# Mechatronic.net
KiCad netlist of a schematic drawn in Altium Designer
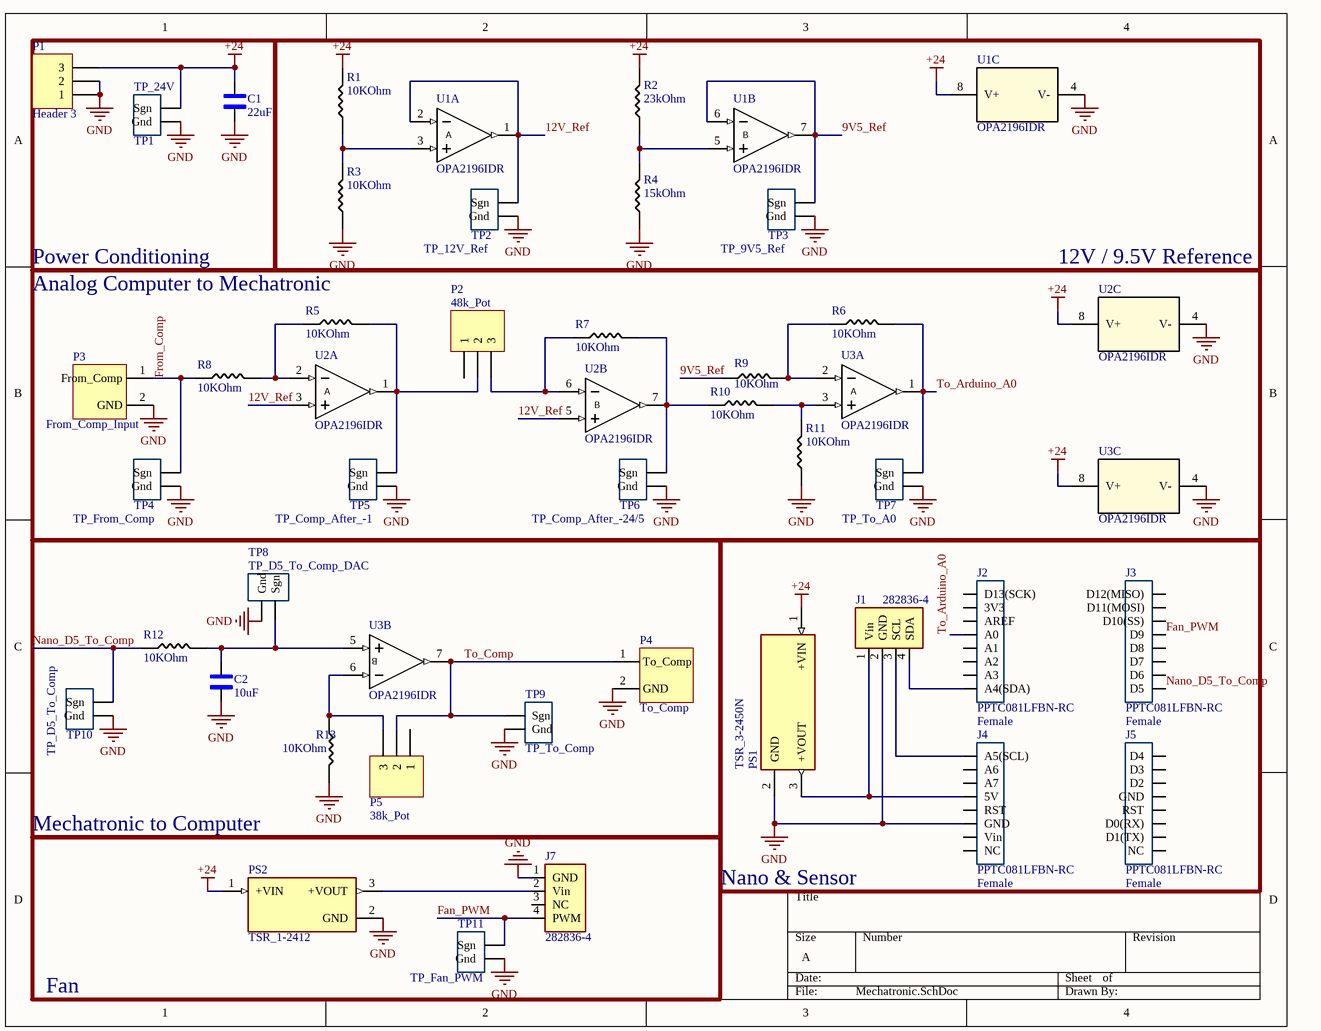
[diagram p0: Mechatronic.SchDoc]

(export (version "E")
  (design (tool "Eeschema 10.0.6"))
  (components
    (comp (ref "C1")
      (value "22uF")
      (footprint "1206_Passive_Capacitor")
      (description "22uF ±10% 25V X5R 1206 Multilayer Ceramic Capacitors MLCC - SMD/SMT RoHS")
      (fields (field (name "MFR PART #") "CL31A226KAHNNNE") (field (name "LCSC PART#") "C12891"))
      (libsource (lib "ECEN5730Lib_2023_05_DS") (part "C_22uF_1206"))
    )
    (comp (ref "C2")
      (value "10uF")
      (footprint "1206_Passive_Capacitor")
      (description "10uF ±10% 50V X5R 1206 Multilayer Ceramic Capacitors MLCC - SMD/SMT RoHS")
      (fields (field (name "LCSC PART#") "C13585") (field (name "MFR PART #") "CL31A106KBHNNNE"))
      (libsource (lib "ECEN5730Lib_2023_05_DS") (part "C_10uF_1206"))
    )
    (comp (ref "J1")
      (value "282836-4")
      (footprint "TE_282836-4")
      (description "4 Position Wire to Board Terminal Block Horizontal with Board 0.197 (5.00mm) Through Hole")
      (fields (field (name "MF") "TE Connectivity"))
      (libsource (lib "") (part "282836-4_1"))
    )
    (comp (ref "J2")
      (value "PPTC081LFBN-RC")
      (footprint "8_PIN_100MIL - Female")
      (description "8 Position Header Connector 0.100\" (2.54mm) Through Hole Tin")
      (fields (field (name "LCSC PART#") "C27438") (field (name "ALTIUM_VALUE") "Female"))
      (libsource (lib "") (part "JF_8_PIN_FEMALE_3"))
    )
    (comp (ref "J3")
      (value "PPTC081LFBN-RC")
      (footprint "8_PIN_100MIL - Female")
      (description "8 Position Header Connector 0.100\" (2.54mm) Through Hole Tin")
      (fields (field (name "LCSC PART#") "C27438") (field (name "ALTIUM_VALUE") "Female"))
      (libsource (lib "ECEN5730Lib_2023_05_DS") (part "JF_8_PIN_FEMALE"))
    )
    (comp (ref "J4")
      (value "PPTC081LFBN-RC")
      (footprint "8_PIN_100MIL - Female")
      (description "8 Position Header Connector 0.100\" (2.54mm) Through Hole Tin")
      (fields (field (name "LCSC PART#") "C27438") (field (name "ALTIUM_VALUE") "Female"))
      (libsource (lib "") (part "JF_8_PIN_FEMALE_1"))
    )
    (comp (ref "J5")
      (value "PPTC081LFBN-RC")
      (footprint "8_PIN_100MIL - Female")
      (description "8 Position Header Connector 0.100\" (2.54mm) Through Hole Tin")
      (fields (field (name "LCSC PART#") "C27438") (field (name "ALTIUM_VALUE") "Female"))
      (libsource (lib "") (part "JF_8_PIN_FEMALE_2"))
    )
    (comp (ref "J7")
      (value "282836-4")
      (footprint "TE_282836-4")
      (description "4 Position Wire to Board Terminal Block Horizontal with Board 0.197 (5.00mm) Through Hole")
      (fields (field (name "MF") "TE Connectivity"))
      (libsource (lib "282836-4") (part "282836-4"))
    )
    (comp (ref "P1")
      (value "Header 3")
      (footprint "HDR1X3")
      (description "Header, 3-Pin")
      (fields (field (name "PUBLISHER") "Altium Limited"))
      (libsource (lib "") (part "Header 3_1"))
    )
    (comp (ref "P2")
      (value "48k_Pot")
      (footprint "HDR1X3")
      (description "Header, 3-Pin")
      (fields (field (name "PUBLISHER") "Altium Limited"))
      (libsource (lib "") (part "Header 3_2"))
    )
    (comp (ref "P3")
      (value "From_Comp_Input")
      (footprint "P_Terminal block 3.5mm-pitch")
      (description "Green Straight pin 3.5mm  pitch; P=3.5mm  Screw terminal ROHS")
      (fields (field (name "MFR PART #") "KF350-3.5-2P") (field (name "MANUFACTURER") "Cixi Kefa Elec"))
      (libsource (lib "") (part "P_Terminal block_1"))
    )
    (comp (ref "P4")
      (value "To_Comp")
      (footprint "P_Terminal block 3.5mm-pitch")
      (description "Green Straight pin 3.5mm  pitch; P=3.5mm  Screw terminal ROHS")
      (fields (field (name "MFR PART #") "KF350-3.5-2P") (field (name "MANUFACTURER") "Cixi Kefa Elec"))
      (libsource (lib "ECEN5730Lib_2023_05_DS") (part "P_Terminal block"))
    )
    (comp (ref "P5")
      (value "38k_Pot")
      (footprint "HDR1X3")
      (description "Header, 3-Pin")
      (fields (field (name "PUBLISHER") "Altium Limited"))
      (libsource (lib "Miscellaneous Connectors") (part "Header 3"))
    )
    (comp (ref "PS1")
      (value "TSR_3-2450N")
      (footprint "CONV_TSR_3-2450N")
      (fields (field (name "MF") "{'manufacturer': u'Traco Power'}"))
      (libsource (lib "TSR_3-2450N") (part "TSR_3-2450N"))
    )
    (comp (ref "PS2")
      (value "TSR_1-2412")
      (footprint "CONV_TSR_1-2412")
      (libsource (lib "TSR_1-2412") (part "TSR_1-2412"))
    )
    (comp (ref "R1")
      (value "10KOhm")
      (footprint "1206_Passive_Resitor")
      (description "10 kOhms ±5% 0.25W, 1/4W Chip Resistor 1206 (3216 Metric) Automotive AEC-Q200 Thick Film")
      (fields (field (name "MFR PART #") "RMCF1206FT10K0") (field (name "LCSC PART#") "C17902"))
      (libsource (lib "ECEN5730Lib_2023_05_DS") (part "R_10KOhm_1206"))
    )
    (comp (ref "R2")
      (value "23kOhm")
      (footprint "1206_Passive_Resitor")
      (description "CHIP RESISTOR - SURFACE MOUNT 0OHMS ±1% 1/4W 1206 ROHS")
      (fields (field (name "MFR PART #") "1206W4F0000T5E") (field (name "LCSC PART#") "C17888"))
      (libsource (lib "Capstone_Stock_Library_R2") (part "R_0_1206"))
    )
    (comp (ref "R3")
      (value "10KOhm")
      (footprint "1206_Passive_Resitor")
      (description "10 kOhms ±5% 0.25W, 1/4W Chip Resistor 1206 (3216 Metric) Automotive AEC-Q200 Thick Film")
      (fields (field (name "MFR PART #") "RMCF1206FT10K0") (field (name "LCSC PART#") "C17902"))
      (libsource (lib "ECEN5730Lib_2023_05_DS") (part "R_10KOhm_1206"))
    )
    (comp (ref "R4")
      (value "15kOhm")
      (footprint "1206_Passive_Resitor")
      (description "CHIP RESISTOR - SURFACE MOUNT 0OHMS ±1% 1/4W 1206 ROHS")
      (fields (field (name "MFR PART #") "1206W4F0000T5E") (field (name "LCSC PART#") "C17888"))
      (libsource (lib "Capstone_Stock_Library_R2") (part "R_0_1206"))
    )
    (comp (ref "R5")
      (value "10KOhm")
      (footprint "1206_Passive_Resitor")
      (description "10 kOhms ±5% 0.25W, 1/4W Chip Resistor 1206 (3216 Metric) Automotive AEC-Q200 Thick Film")
      (fields (field (name "MFR PART #") "RMCF1206FT10K0") (field (name "LCSC PART#") "C17902"))
      (libsource (lib "ECEN5730Lib_2023_05_DS") (part "R_10KOhm_1206"))
    )
    (comp (ref "R6")
      (value "10KOhm")
      (footprint "1206_Passive_Resitor")
      (description "10 kOhms ±5% 0.25W, 1/4W Chip Resistor 1206 (3216 Metric) Automotive AEC-Q200 Thick Film")
      (fields (field (name "MFR PART #") "RMCF1206FT10K0") (field (name "LCSC PART#") "C17902"))
      (libsource (lib "ECEN5730Lib_2023_05_DS") (part "R_10KOhm_1206"))
    )
    (comp (ref "R7")
      (value "10KOhm")
      (footprint "1206_Passive_Resitor")
      (description "10 kOhms ±5% 0.25W, 1/4W Chip Resistor 1206 (3216 Metric) Automotive AEC-Q200 Thick Film")
      (fields (field (name "MFR PART #") "RMCF1206FT10K0") (field (name "LCSC PART#") "C17902"))
      (libsource (lib "ECEN5730Lib_2023_05_DS") (part "R_10KOhm_1206"))
    )
    (comp (ref "R8")
      (value "10KOhm")
      (footprint "1206_Passive_Resitor")
      (description "10 kOhms ±5% 0.25W, 1/4W Chip Resistor 1206 (3216 Metric) Automotive AEC-Q200 Thick Film")
      (fields (field (name "MFR PART #") "RMCF1206FT10K0") (field (name "LCSC PART#") "C17902"))
      (libsource (lib "ECEN5730Lib_2023_05_DS") (part "R_10KOhm_1206"))
    )
    (comp (ref "R9")
      (value "10KOhm")
      (footprint "1206_Passive_Resitor")
      (description "10 kOhms ±5% 0.25W, 1/4W Chip Resistor 1206 (3216 Metric) Automotive AEC-Q200 Thick Film")
      (fields (field (name "MFR PART #") "RMCF1206FT10K0") (field (name "LCSC PART#") "C17902"))
      (libsource (lib "ECEN5730Lib_2023_05_DS") (part "R_10KOhm_1206"))
    )
    (comp (ref "R10")
      (value "10KOhm")
      (footprint "1206_Passive_Resitor")
      (description "10 kOhms ±5% 0.25W, 1/4W Chip Resistor 1206 (3216 Metric) Automotive AEC-Q200 Thick Film")
      (fields (field (name "MFR PART #") "RMCF1206FT10K0") (field (name "LCSC PART#") "C17902"))
      (libsource (lib "ECEN5730Lib_2023_05_DS") (part "R_10KOhm_1206"))
    )
    (comp (ref "R11")
      (value "10KOhm")
      (footprint "1206_Passive_Resitor")
      (description "10 kOhms ±5% 0.25W, 1/4W Chip Resistor 1206 (3216 Metric) Automotive AEC-Q200 Thick Film")
      (fields (field (name "MFR PART #") "RMCF1206FT10K0") (field (name "LCSC PART#") "C17902"))
      (libsource (lib "ECEN5730Lib_2023_05_DS") (part "R_10KOhm_1206"))
    )
    (comp (ref "R12")
      (value "10KOhm")
      (footprint "1206_Passive_Resitor")
      (description "10 kOhms ±5% 0.25W, 1/4W Chip Resistor 1206 (3216 Metric) Automotive AEC-Q200 Thick Film")
      (fields (field (name "MFR PART #") "RMCF1206FT10K0") (field (name "LCSC PART#") "C17902"))
      (libsource (lib "ECEN5730Lib_2023_05_DS") (part "R_10KOhm_1206"))
    )
    (comp (ref "R13")
      (value "10KOhm")
      (footprint "1206_Passive_Resitor")
      (description "10 kOhms ±5% 0.25W, 1/4W Chip Resistor 1206 (3216 Metric) Automotive AEC-Q200 Thick Film")
      (fields (field (name "MFR PART #") "RMCF1206FT10K0") (field (name "LCSC PART#") "C17902"))
      (libsource (lib "ECEN5730Lib_2023_05_DS") (part "R_10KOhm_1206"))
    )
    (comp (ref "TP1")
      (value "TP_24V")
      (footprint "TP10x_Probe")
      (description "Test Point 300 mil centers")
      (libsource (lib "") (part "TP_10x_Probe_1"))
    )
    (comp (ref "TP2")
      (value "TP_12V_Ref")
      (footprint "TP10x_Probe")
      (description "Test Point 300 mil centers")
      (libsource (lib "") (part "TP_10x_Probe_1"))
    )
    (comp (ref "TP3")
      (value "TP_9V5_Ref")
      (footprint "TP10x_Probe")
      (description "Test Point 300 mil centers")
      (libsource (lib "") (part "TP_10x_Probe_1"))
    )
    (comp (ref "TP4")
      (value "TP_From_Comp")
      (footprint "TP10x_Probe")
      (description "Test Point 300 mil centers")
      (libsource (lib "") (part "TP_10x_Probe_1"))
    )
    (comp (ref "TP5")
      (value "TP_Comp_After_-1")
      (footprint "TP10x_Probe")
      (description "Test Point 300 mil centers")
      (libsource (lib "") (part "TP_10x_Probe_1"))
    )
    (comp (ref "TP6")
      (value "TP_Comp_After_-24/5")
      (footprint "TP10x_Probe")
      (description "Test Point 300 mil centers")
      (libsource (lib "") (part "TP_10x_Probe_1"))
    )
    (comp (ref "TP7")
      (value "TP_To_A0")
      (footprint "TP10x_Probe")
      (description "Test Point 300 mil centers")
      (libsource (lib "") (part "TP_10x_Probe_1"))
    )
    (comp (ref "TP8")
      (value "TP_D5_To_Comp_DAC")
      (footprint "TP10x_Probe")
      (description "Test Point 300 mil centers")
      (libsource (lib "ECEN5730Lib_2023_05_DS") (part "TP_10x_Probe"))
    )
    (comp (ref "TP9")
      (value "TP_To_Comp")
      (footprint "TP10x_Probe")
      (description "Test Point 300 mil centers")
      (libsource (lib "ECEN5730Lib_2023_05_DS") (part "TP_10x_Probe"))
    )
    (comp (ref "TP10")
      (value "TP_D5_To_Comp")
      (footprint "TP10x_Probe")
      (description "Test Point 300 mil centers")
      (libsource (lib "") (part "TP_10x_Probe_1"))
    )
    (comp (ref "TP11")
      (value "TP_Fan_PWM")
      (footprint "TP10x_Probe")
      (description "Test Point 300 mil centers")
      (libsource (lib "") (part "TP_10x_Probe_1"))
    )
    (comp (ref "U1")
      (value "OPA2196IDR")
      (footprint "D0008A_N")
      (description "Dual, 36-V, low power, all-purpose amplifier with mux-friendly input 8-SOIC -40 to 125")
      (fields (field (name "COPYRIGHT") "Copyright (C) 2026 Ultra Librarian. All rights reserved."))
      (libsource (lib "Integrated_Library1") (part "OPA2196IDR"))
    )
    (comp (ref "U2")
      (value "OPA2196IDR")
      (footprint "D0008A_N")
      (description "Dual, 36-V, low power, all-purpose amplifier with mux-friendly input 8-SOIC -40 to 125")
      (fields (field (name "COPYRIGHT") "Copyright (C) 2026 Ultra Librarian. All rights reserved."))
      (libsource (lib "Integrated_Library1") (part "OPA2196IDR"))
    )
    (comp (ref "U3")
      (value "OPA2196IDR")
      (footprint "D0008A_N")
      (description "Dual, 36-V, low power, all-purpose amplifier with mux-friendly input 8-SOIC -40 to 125")
      (fields (field (name "COPYRIGHT") "Copyright (C) 2026 Ultra Librarian. All rights reserved."))
      (libsource (lib "Integrated_Library1") (part "OPA2196IDR"))
    )
  )
  (nets
    (net (code "1") (name "+24") (class "Default")
      (node (ref "C1") (pin "2") (pinfunction "2_2") (pintype "passive"))
      (node (ref "P1") (pin "3") (pinfunction "3_3") (pintype "passive"))
      (node (ref "PS1") (pin "1") (pinfunction "+VIN_1") (pintype "input"))
      (node (ref "PS2") (pin "1") (pinfunction "+VIN_1") (pintype "input"))
      (node (ref "R1") (pin "2") (pinfunction "2_2") (pintype "passive"))
      (node (ref "R2") (pin "2") (pinfunction "2_2") (pintype "passive"))
      (node (ref "TP1") (pin "1") (pinfunction "Sgn_1") (pintype "passive"))
      (node (ref "U1") (pin "8") (pinfunction "V+_8") (pintype "power_in"))
      (node (ref "U2") (pin "8") (pinfunction "V+_8") (pintype "power_in"))
      (node (ref "U3") (pin "8") (pinfunction "V+_8") (pintype "power_in"))
    )
    (net (code "2") (name "/9V5_Ref") (class "Default")
      (node (ref "R9") (pin "1") (pinfunction "1_1") (pintype "passive"))
      (node (ref "TP3") (pin "1") (pinfunction "Sgn_1") (pintype "passive"))
      (node (ref "U1") (pin "6") (pinfunction "IN-_6") (pintype "input"))
      (node (ref "U1") (pin "7") (pinfunction "OUT_7") (pintype "output"))
    )
    (net (code "3") (name "/12V_Ref") (class "Default")
      (node (ref "TP2") (pin "1") (pinfunction "Sgn_1") (pintype "passive"))
      (node (ref "U1") (pin "1") (pinfunction "OUT_1") (pintype "output"))
      (node (ref "U1") (pin "2") (pinfunction "IN-_2") (pintype "input"))
      (node (ref "U2") (pin "3") (pinfunction "IN+_3") (pintype "input"))
      (node (ref "U2") (pin "5") (pinfunction "IN+_5") (pintype "input"))
    )
    (net (code "4") (name "/Fan_PWM") (class "Default")
      (node (ref "J3") (pin "5") (pinfunction "D9_5") (pintype "passive"))
      (node (ref "J7") (pin "4") (pinfunction "PWM_4") (pintype "passive"))
      (node (ref "TP11") (pin "1") (pinfunction "Sgn_1") (pintype "passive"))
    )
    (net (code "5") (name "/From_Comp") (class "Default")
      (node (ref "P3") (pin "1") (pinfunction "From_Comp_1") (pintype "passive"))
      (node (ref "R8") (pin "1") (pinfunction "1_1") (pintype "passive"))
      (node (ref "TP4") (pin "1") (pinfunction "Sgn_1") (pintype "passive"))
    )
    (net (code "6") (name "/Nano_D5_To_Comp") (class "Default")
      (node (ref "J3") (pin "1") (pinfunction "D5_1") (pintype "passive"))
      (node (ref "R12") (pin "1") (pinfunction "1_1") (pintype "passive"))
      (node (ref "TP10") (pin "1") (pinfunction "Sgn_1") (pintype "passive"))
    )
    (net (code "7") (name "/To_Arduino_A0") (class "Default")
      (node (ref "J2") (pin "5") (pinfunction "A0_5") (pintype "passive"))
      (node (ref "R6") (pin "2") (pinfunction "2_2") (pintype "passive"))
      (node (ref "TP7") (pin "1") (pinfunction "Sgn_1") (pintype "passive"))
      (node (ref "U3") (pin "1") (pinfunction "OUT_1") (pintype "output"))
    )
    (net (code "8") (name "/To_Comp") (class "Default")
      (node (ref "P4") (pin "1") (pinfunction "To_Comp_1") (pintype "passive"))
      (node (ref "P5") (pin "2") (pinfunction "2_2") (pintype "passive"))
      (node (ref "TP9") (pin "1") (pinfunction "Sgn_1") (pintype "passive"))
      (node (ref "U3") (pin "7") (pinfunction "OUT_7") (pintype "output"))
    )
    (net (code "9") (name "GND") (class "Default")
      (node (ref "C1") (pin "1") (pinfunction "1_1") (pintype "passive"))
      (node (ref "C2") (pin "1") (pinfunction "1_1") (pintype "passive"))
      (node (ref "J1") (pin "2") (pinfunction "GND_2") (pintype "passive"))
      (node (ref "J4") (pin "6") (pinfunction "GND_6") (pintype "passive"))
      (node (ref "J7") (pin "1") (pinfunction "GND_1") (pintype "passive"))
      (node (ref "P1") (pin "1") (pinfunction "1_1") (pintype "passive"))
      (node (ref "P1") (pin "2") (pinfunction "2_2") (pintype "passive"))
      (node (ref "P3") (pin "2") (pinfunction "GND_2") (pintype "passive"))
      (node (ref "P4") (pin "2") (pinfunction "GND_2") (pintype "passive"))
      (node (ref "PS1") (pin "2") (pinfunction "GND_2") (pintype "power_in"))
      (node (ref "PS2") (pin "2") (pinfunction "GND_2") (pintype "power_in"))
      (node (ref "R11") (pin "1") (pinfunction "1_1") (pintype "passive"))
      (node (ref "R13") (pin "2") (pinfunction "2_2") (pintype "passive"))
      (node (ref "R3") (pin "1") (pinfunction "1_1") (pintype "passive"))
      (node (ref "R4") (pin "1") (pinfunction "1_1") (pintype "passive"))
      (node (ref "TP1") (pin "2") (pinfunction "Gnd_2") (pintype "passive"))
      (node (ref "TP10") (pin "2") (pinfunction "Gnd_2") (pintype "passive"))
      (node (ref "TP11") (pin "2") (pinfunction "Gnd_2") (pintype "passive"))
      (node (ref "TP2") (pin "2") (pinfunction "Gnd_2") (pintype "passive"))
      (node (ref "TP3") (pin "2") (pinfunction "Gnd_2") (pintype "passive"))
      (node (ref "TP4") (pin "2") (pinfunction "Gnd_2") (pintype "passive"))
      (node (ref "TP5") (pin "2") (pinfunction "Gnd_2") (pintype "passive"))
      (node (ref "TP6") (pin "2") (pinfunction "Gnd_2") (pintype "passive"))
      (node (ref "TP7") (pin "2") (pinfunction "Gnd_2") (pintype "passive"))
      (node (ref "TP8") (pin "2") (pinfunction "Gnd_2") (pintype "passive"))
      (node (ref "TP9") (pin "2") (pinfunction "Gnd_2") (pintype "passive"))
      (node (ref "U1") (pin "4") (pinfunction "V-_4") (pintype "power_in"))
      (node (ref "U2") (pin "4") (pinfunction "V-_4") (pintype "power_in"))
      (node (ref "U3") (pin "4") (pinfunction "V-_4") (pintype "power_in"))
    )
    (net (code "10") (name "Net-(J1-SCL)") (class "Default")
      (node (ref "J1") (pin "3") (pinfunction "SCL_3") (pintype "passive"))
      (node (ref "J4") (pin "1") (pinfunction "A5(SCL)_1") (pintype "passive"))
    )
    (net (code "11") (name "Net-(J1-SDA)") (class "Default")
      (node (ref "J1") (pin "4") (pinfunction "SDA_4") (pintype "passive"))
      (node (ref "J2") (pin "1") (pinfunction "A4(SDA)_1") (pintype "passive"))
    )
    (net (code "12") (name "Net-(J1-Vin)") (class "Default")
      (node (ref "J1") (pin "1") (pinfunction "Vin_1") (pintype "passive"))
      (node (ref "J4") (pin "4") (pinfunction "5V_4") (pintype "passive"))
      (node (ref "PS1") (pin "3") (pinfunction "+VOUT_3") (pintype "output"))
    )
    (net (code "13") (name "Net-(J7-Vin)") (class "Default")
      (node (ref "J7") (pin "2") (pinfunction "Vin_2") (pintype "passive"))
      (node (ref "PS2") (pin "3") (pinfunction "+VOUT_3") (pintype "output"))
    )
    (net (code "14") (name "Net-(TP5-Sgn)") (class "Default")
      (node (ref "P2") (pin "2") (pinfunction "2_2") (pintype "passive"))
      (node (ref "R5") (pin "2") (pinfunction "2_2") (pintype "passive"))
      (node (ref "TP5") (pin "1") (pinfunction "Sgn_1") (pintype "passive"))
      (node (ref "U2") (pin "1") (pinfunction "OUT_1") (pintype "output"))
    )
    (net (code "15") (name "Net-(TP6-Sgn)") (class "Default")
      (node (ref "R10") (pin "1") (pinfunction "1_1") (pintype "passive"))
      (node (ref "R7") (pin "2") (pinfunction "2_2") (pintype "passive"))
      (node (ref "TP6") (pin "1") (pinfunction "Sgn_1") (pintype "passive"))
      (node (ref "U2") (pin "7") (pinfunction "OUT_7") (pintype "output"))
    )
    (net (code "16") (name "Net-(TP8-Sgn)") (class "Default")
      (node (ref "C2") (pin "2") (pinfunction "2_2") (pintype "passive"))
      (node (ref "R12") (pin "2") (pinfunction "2_2") (pintype "passive"))
      (node (ref "TP8") (pin "1") (pinfunction "Sgn_1") (pintype "passive"))
      (node (ref "U3") (pin "5") (pinfunction "IN+_5") (pintype "input"))
    )
    (net (code "17") (name "Net-(U1A-IN+)") (class "Default")
      (node (ref "R1") (pin "1") (pinfunction "1_1") (pintype "passive"))
      (node (ref "R3") (pin "2") (pinfunction "2_2") (pintype "passive"))
      (node (ref "U1") (pin "3") (pinfunction "IN+_3") (pintype "input"))
    )
    (net (code "18") (name "Net-(U1B-IN+)") (class "Default")
      (node (ref "R2") (pin "1") (pinfunction "1_1") (pintype "passive"))
      (node (ref "R4") (pin "2") (pinfunction "2_2") (pintype "passive"))
      (node (ref "U1") (pin "5") (pinfunction "IN+_5") (pintype "input"))
    )
    (net (code "19") (name "Net-(U2A-IN-)") (class "Default")
      (node (ref "R5") (pin "1") (pinfunction "1_1") (pintype "passive"))
      (node (ref "R8") (pin "2") (pinfunction "2_2") (pintype "passive"))
      (node (ref "U2") (pin "2") (pinfunction "IN-_2") (pintype "input"))
    )
    (net (code "20") (name "Net-(U2B-IN-)") (class "Default")
      (node (ref "P2") (pin "3") (pinfunction "3_3") (pintype "passive"))
      (node (ref "R7") (pin "1") (pinfunction "1_1") (pintype "passive"))
      (node (ref "U2") (pin "6") (pinfunction "IN-_6") (pintype "input"))
    )
    (net (code "21") (name "Net-(U3A-IN+)") (class "Default")
      (node (ref "R10") (pin "2") (pinfunction "2_2") (pintype "passive"))
      (node (ref "R11") (pin "2") (pinfunction "2_2") (pintype "passive"))
      (node (ref "U3") (pin "3") (pinfunction "IN+_3") (pintype "input"))
    )
    (net (code "22") (name "Net-(U3A-IN-)") (class "Default")
      (node (ref "R6") (pin "1") (pinfunction "1_1") (pintype "passive"))
      (node (ref "R9") (pin "2") (pinfunction "2_2") (pintype "passive"))
      (node (ref "U3") (pin "2") (pinfunction "IN-_2") (pintype "input"))
    )
    (net (code "23") (name "Net-(U3B-IN-)") (class "Default")
      (node (ref "P5") (pin "3") (pinfunction "3_3") (pintype "passive"))
      (node (ref "R13") (pin "1") (pinfunction "1_1") (pintype "passive"))
      (node (ref "U3") (pin "6") (pinfunction "IN-_6") (pintype "input"))
    )
    (net (code "24") (name "unconnected-(J2-3V3-Pad7)") (class "Default")
      (node (ref "J2") (pin "7") (pinfunction "3V3_7") (pintype "passive"))
    )
    (net (code "25") (name "unconnected-(J2-A1-Pad4)") (class "Default")
      (node (ref "J2") (pin "4") (pinfunction "A1_4") (pintype "passive"))
    )
    (net (code "26") (name "unconnected-(J2-A2-Pad3)") (class "Default")
      (node (ref "J2") (pin "3") (pinfunction "A2_3") (pintype "passive"))
    )
    (net (code "27") (name "unconnected-(J2-A3-Pad2)") (class "Default")
      (node (ref "J2") (pin "2") (pinfunction "A3_2") (pintype "passive"))
    )
    (net (code "28") (name "unconnected-(J2-AREF-Pad6)") (class "Default")
      (node (ref "J2") (pin "6") (pinfunction "AREF_6") (pintype "passive"))
    )
    (net (code "29") (name "unconnected-(J2-D13(SCK)-Pad8)") (class "Default")
      (node (ref "J2") (pin "8") (pinfunction "D13(SCK)_8") (pintype "passive"))
    )
    (net (code "30") (name "unconnected-(J3-D6-Pad2)") (class "Default")
      (node (ref "J3") (pin "2") (pinfunction "D6_2") (pintype "passive"))
    )
    (net (code "31") (name "unconnected-(J3-D7-Pad3)") (class "Default")
      (node (ref "J3") (pin "3") (pinfunction "D7_3") (pintype "passive"))
    )
    (net (code "32") (name "unconnected-(J3-D8-Pad4)") (class "Default")
      (node (ref "J3") (pin "4") (pinfunction "D8_4") (pintype "passive"))
    )
    (net (code "33") (name "unconnected-(J3-D10(SS)-Pad6)") (class "Default")
      (node (ref "J3") (pin "6") (pinfunction "D10(SS)_6") (pintype "passive"))
    )
    (net (code "34") (name "unconnected-(J3-D11(MOSI)-Pad7)") (class "Default")
      (node (ref "J3") (pin "7") (pinfunction "D11(MOSI)_7") (pintype "passive"))
    )
    (net (code "35") (name "unconnected-(J3-D12(MISO)-Pad8)") (class "Default")
      (node (ref "J3") (pin "8") (pinfunction "D12(MISO)_8") (pintype "passive"))
    )
    (net (code "36") (name "unconnected-(J4-A6-Pad2)") (class "Default")
      (node (ref "J4") (pin "2") (pinfunction "A6_2") (pintype "passive"))
    )
    (net (code "37") (name "unconnected-(J4-A7-Pad3)") (class "Default")
      (node (ref "J4") (pin "3") (pinfunction "A7_3") (pintype "passive"))
    )
    (net (code "38") (name "unconnected-(J4-NC-Pad8)") (class "Default")
      (node (ref "J4") (pin "8") (pinfunction "NC_8") (pintype "passive"))
    )
    (net (code "39") (name "unconnected-(J4-RST-Pad5)") (class "Default")
      (node (ref "J4") (pin "5") (pinfunction "RST_5") (pintype "passive"))
    )
    (net (code "40") (name "unconnected-(J4-Vin-Pad7)") (class "Default")
      (node (ref "J4") (pin "7") (pinfunction "Vin_7") (pintype "passive"))
    )
    (net (code "41") (name "unconnected-(J5-D0(RX)-Pad6)") (class "Default")
      (node (ref "J5") (pin "6") (pinfunction "D0(RX)_6") (pintype "passive"))
    )
    (net (code "42") (name "unconnected-(J5-D1(TX)-Pad7)") (class "Default")
      (node (ref "J5") (pin "7") (pinfunction "D1(TX)_7") (pintype "passive"))
    )
    (net (code "43") (name "unconnected-(J5-D2-Pad3)") (class "Default")
      (node (ref "J5") (pin "3") (pinfunction "D2_3") (pintype "passive"))
    )
    (net (code "44") (name "unconnected-(J5-D3-Pad2)") (class "Default")
      (node (ref "J5") (pin "2") (pinfunction "D3_2") (pintype "passive"))
    )
    (net (code "45") (name "unconnected-(J5-D4-Pad1)") (class "Default")
      (node (ref "J5") (pin "1") (pinfunction "D4_1") (pintype "passive"))
    )
    (net (code "46") (name "unconnected-(J5-GND-Pad4)") (class "Default")
      (node (ref "J5") (pin "4") (pinfunction "GND_4") (pintype "passive"))
    )
    (net (code "47") (name "unconnected-(J5-NC-Pad8)") (class "Default")
      (node (ref "J5") (pin "8") (pinfunction "NC_8") (pintype "passive"))
    )
    (net (code "48") (name "unconnected-(J5-RST-Pad5)") (class "Default")
      (node (ref "J5") (pin "5") (pinfunction "RST_5") (pintype "passive"))
    )
    (net (code "49") (name "unconnected-(J7-NC-Pad3)") (class "Default")
      (node (ref "J7") (pin "3") (pinfunction "NC_3") (pintype "passive"))
    )
    (net (code "50") (name "unconnected-(P2-Pad1)") (class "Default")
      (node (ref "P2") (pin "1") (pinfunction "1_1") (pintype "passive"))
    )
    (net (code "51") (name "unconnected-(P5-Pad1)") (class "Default")
      (node (ref "P5") (pin "1") (pinfunction "1_1") (pintype "passive"))
    )
  )
)
